# breakout.net
KiCad netlist of a schematic drawn in EAGLE
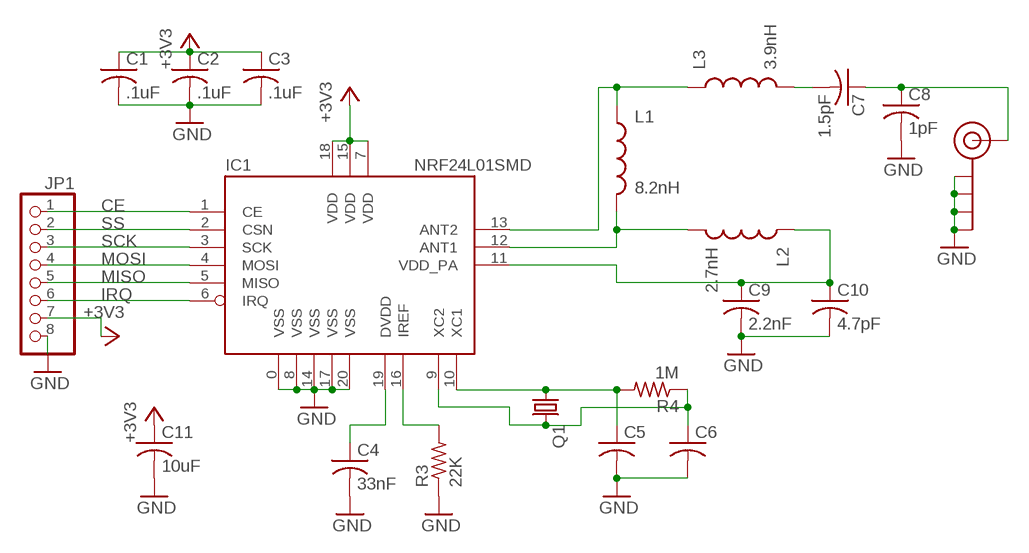
[diagram p0: schematic, sheet 1]

(export (version "E")
  (design (tool "Eeschema 10.0.6"))
  (components
    (comp (ref "C1")
      (value ".1uF")
      (footprint "eagle-import:C0402")
      (libsource (lib "eagle-import") (part "C-USC0402"))
    )
    (comp (ref "C2")
      (value ".1uF")
      (footprint "eagle-import:C0402")
      (libsource (lib "eagle-import") (part "C-USC0402"))
    )
    (comp (ref "C3")
      (value ".1uF")
      (footprint "eagle-import:C0402")
      (libsource (lib "eagle-import") (part "C-USC0402"))
    )
    (comp (ref "C4")
      (value "33nF")
      (footprint "eagle-import:C0402")
      (libsource (lib "eagle-import") (part "C-USC0402"))
    )
    (comp (ref "C5")
      (value "C-USC0402")
      (footprint "eagle-import:C0402")
      (libsource (lib "eagle-import") (part "C-USC0402"))
    )
    (comp (ref "C6")
      (value "C-USC0402")
      (footprint "eagle-import:C0402")
      (libsource (lib "eagle-import") (part "C-USC0402"))
    )
    (comp (ref "C7")
      (value "1.5pF")
      (footprint "eagle-import:C0402")
      (libsource (lib "eagle-import") (part "C-USC0402"))
    )
    (comp (ref "C8")
      (value "1pF")
      (footprint "eagle-import:C0402")
      (libsource (lib "eagle-import") (part "C-USC0402"))
    )
    (comp (ref "C9")
      (value "2.2nF")
      (footprint "eagle-import:C0402")
      (libsource (lib "eagle-import") (part "C-USC0402"))
    )
    (comp (ref "C10")
      (value "4.7pF")
      (footprint "eagle-import:C0402")
      (libsource (lib "eagle-import") (part "C-USC0402"))
    )
    (comp (ref "C11")
      (value "10uF")
      (footprint "eagle-import:C0805K")
      (libsource (lib "eagle-import") (part "C-USC0805K"))
    )
    (comp (ref "IC1")
      (value "NRF24L01SMD")
      (footprint "eagle-import:QFN20")
      (libsource (lib "eagle-import") (part "NRF24L01SMD"))
    )
    (comp (ref "J$1")
      (value "SMA_EDGE")
      (footprint "eagle-import:SMA-EDGE")
      (libsource (lib "eagle-import") (part "SMA_EDGE"))
    )
    (comp (ref "JP1")
      (value "PINHD-1X8")
      (footprint "eagle-import:1X08")
      (libsource (lib "eagle-import") (part "PINHD-1X8"))
    )
    (comp (ref "L1")
      (value "8.2nH")
      (footprint "eagle-import:C0402")
      (libsource (lib "eagle-import") (part "INDUCTOR0402"))
    )
    (comp (ref "L2")
      (value "2.7nH")
      (footprint "eagle-import:C0402")
      (libsource (lib "eagle-import") (part "INDUCTOR0402"))
    )
    (comp (ref "L3")
      (value "3.9nH")
      (footprint "eagle-import:C0402")
      (libsource (lib "eagle-import") (part "INDUCTOR0402"))
    )
    (comp (ref "Q1")
      (value "CRYSTALHC49U-V")
      (footprint "eagle-import:HC49U-V")
      (libsource (lib "eagle-import") (part "CRYSTALHC49U-V"))
    )
    (comp (ref "R3")
      (value "22K")
      (footprint "eagle-import:R0402")
      (libsource (lib "eagle-import") (part "R-US_R0402"))
    )
    (comp (ref "R4")
      (value "1M")
      (footprint "eagle-import:R0402")
      (libsource (lib "eagle-import") (part "R-US_R0402"))
    )
  )
  (nets
    (net (code "1") (name "+3V3") (class "Default")
      (node (ref "C1") (pin "1") (pinfunction "1_1") (pintype "passive"))
      (node (ref "C11") (pin "1") (pinfunction "1_1") (pintype "passive"))
      (node (ref "C2") (pin "1") (pinfunction "1_1") (pintype "passive"))
      (node (ref "C3") (pin "1") (pinfunction "1_1") (pintype "passive"))
      (node (ref "IC1") (pin "15") (pinfunction "VDD_15") (pintype "power_in"))
      (node (ref "IC1") (pin "18") (pinfunction "VDD_18") (pintype "power_in"))
      (node (ref "IC1") (pin "7") (pinfunction "VDD_7") (pintype "power_in"))
      (node (ref "JP1") (pin "7") (pinfunction "7_7") (pintype "passive"))
    )
    (net (code "2") (name "/CE") (class "Default")
      (node (ref "IC1") (pin "1") (pinfunction "CE_1") (pintype "input"))
      (node (ref "JP1") (pin "1") (pinfunction "1_1") (pintype "passive"))
    )
    (net (code "3") (name "/IRQ") (class "Default")
      (node (ref "IC1") (pin "6") (pinfunction "IRQ_6") (pintype "output"))
      (node (ref "JP1") (pin "6") (pinfunction "6_6") (pintype "passive"))
    )
    (net (code "4") (name "/MISO") (class "Default")
      (node (ref "IC1") (pin "5") (pinfunction "MISO_5") (pintype "output"))
      (node (ref "JP1") (pin "5") (pinfunction "5_5") (pintype "passive"))
    )
    (net (code "5") (name "/MOSI") (class "Default")
      (node (ref "IC1") (pin "4") (pinfunction "MOSI_4") (pintype "input"))
      (node (ref "JP1") (pin "4") (pinfunction "4_4") (pintype "passive"))
    )
    (net (code "6") (name "/SCK") (class "Default")
      (node (ref "IC1") (pin "3") (pinfunction "SCK_3") (pintype "input"))
      (node (ref "JP1") (pin "3") (pinfunction "3_3") (pintype "passive"))
    )
    (net (code "7") (name "/SS") (class "Default")
      (node (ref "IC1") (pin "2") (pinfunction "CSN_2") (pintype "input"))
      (node (ref "JP1") (pin "2") (pinfunction "2_2") (pintype "passive"))
    )
    (net (code "8") (name "GND") (class "Default")
      (node (ref "C1") (pin "2") (pinfunction "2_2") (pintype "passive"))
      (node (ref "C10") (pin "2") (pinfunction "2_2") (pintype "passive"))
      (node (ref "C11") (pin "2") (pinfunction "2_2") (pintype "passive"))
      (node (ref "C2") (pin "2") (pinfunction "2_2") (pintype "passive"))
      (node (ref "C3") (pin "2") (pinfunction "2_2") (pintype "passive"))
      (node (ref "C4") (pin "2") (pinfunction "2_2") (pintype "passive"))
      (node (ref "C5") (pin "2") (pinfunction "2_2") (pintype "passive"))
      (node (ref "C6") (pin "2") (pinfunction "2_2") (pintype "passive"))
      (node (ref "C8") (pin "2") (pinfunction "2_2") (pintype "passive"))
      (node (ref "C9") (pin "2") (pinfunction "2_2") (pintype "passive"))
      (node (ref "IC1") (pin "0") (pinfunction "VSS_0") (pintype "power_in"))
      (node (ref "IC1") (pin "14") (pinfunction "VSS_14") (pintype "power_in"))
      (node (ref "IC1") (pin "17") (pinfunction "VSS_17") (pintype "power_in"))
      (node (ref "IC1") (pin "20") (pinfunction "VSS_20") (pintype "power_in"))
      (node (ref "IC1") (pin "8") (pinfunction "VSS_8") (pintype "power_in"))
      (node (ref "J$1") (pin "GND@0") (pinfunction "GND_GND@0") (pintype "bidirectional"))
      (node (ref "J$1") (pin "GND@1") (pinfunction "GND_GND@1") (pintype "bidirectional"))
      (node (ref "J$1") (pin "GND@2") (pinfunction "GND_GND@2") (pintype "bidirectional"))
      (node (ref "J$1") (pin "GND@3") (pinfunction "GND_GND@3") (pintype "bidirectional"))
      (node (ref "JP1") (pin "8") (pinfunction "8_8") (pintype "passive"))
      (node (ref "R3") (pin "1") (pinfunction "1_1") (pintype "passive"))
    )
    (net (code "9") (name "Net-(C7-Pad2)") (class "Default")
      (node (ref "C7") (pin "2") (pinfunction "2_2") (pintype "passive"))
      (node (ref "L3") (pin "2") (pinfunction "2_2") (pintype "passive"))
    )
    (net (code "10") (name "Net-(IC1-ANT1)") (class "Default")
      (node (ref "IC1") (pin "12") (pinfunction "ANT1_12") (pintype "output"))
      (node (ref "L1") (pin "2") (pinfunction "2_2") (pintype "passive"))
      (node (ref "L2") (pin "2") (pinfunction "2_2") (pintype "passive"))
    )
    (net (code "11") (name "Net-(IC1-ANT2)") (class "Default")
      (node (ref "IC1") (pin "13") (pinfunction "ANT2_13") (pintype "output"))
      (node (ref "L1") (pin "1") (pinfunction "1_1") (pintype "passive"))
      (node (ref "L3") (pin "1") (pinfunction "1_1") (pintype "passive"))
    )
    (net (code "12") (name "Net-(IC1-DVDD)") (class "Default")
      (node (ref "C4") (pin "1") (pinfunction "1_1") (pintype "passive"))
      (node (ref "IC1") (pin "19") (pinfunction "DVDD_19") (pintype "power_in"))
    )
    (net (code "13") (name "Net-(IC1-IREF)") (class "Default")
      (node (ref "IC1") (pin "16") (pinfunction "IREF_16") (pintype "input"))
      (node (ref "R3") (pin "2") (pinfunction "2_2") (pintype "passive"))
    )
    (net (code "14") (name "Net-(IC1-VDD_PA)") (class "Default")
      (node (ref "C10") (pin "1") (pinfunction "1_1") (pintype "passive"))
      (node (ref "C9") (pin "1") (pinfunction "1_1") (pintype "passive"))
      (node (ref "IC1") (pin "11") (pinfunction "VDD_PA_11") (pintype "power_in"))
      (node (ref "L2") (pin "1") (pinfunction "1_1") (pintype "passive"))
    )
    (net (code "15") (name "Net-(IC1-XC1)") (class "Default")
      (node (ref "C5") (pin "1") (pinfunction "1_1") (pintype "passive"))
      (node (ref "IC1") (pin "10") (pinfunction "XC1_10") (pintype "input"))
      (node (ref "Q1") (pin "1") (pinfunction "1_1") (pintype "passive"))
      (node (ref "R4") (pin "2") (pinfunction "2_2") (pintype "passive"))
    )
    (net (code "16") (name "Net-(IC1-XC2)") (class "Default")
      (node (ref "C6") (pin "1") (pinfunction "1_1") (pintype "passive"))
      (node (ref "IC1") (pin "9") (pinfunction "XC2_9") (pintype "input"))
      (node (ref "Q1") (pin "2") (pinfunction "2_2") (pintype "passive"))
      (node (ref "R4") (pin "1") (pinfunction "1_1") (pintype "passive"))
    )
    (net (code "17") (name "Net-(J$1-SIGNAL)") (class "Default")
      (node (ref "C7") (pin "1") (pinfunction "1_1") (pintype "passive"))
      (node (ref "C8") (pin "1") (pinfunction "1_1") (pintype "passive"))
      (node (ref "J$1") (pin "SIG") (pinfunction "SIGNAL_SIG") (pintype "bidirectional"))
    )
  )
)
